# DIGITAL_OUTPUT_2CH.net
KiCad netlist of a schematic drawn in Altium Designer
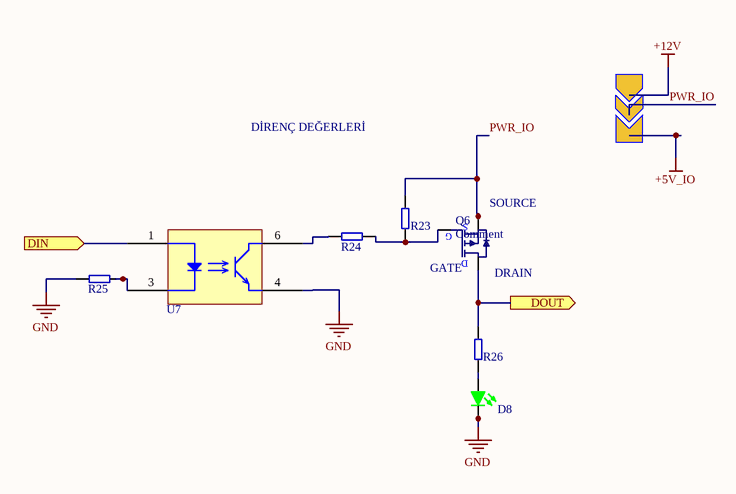
[diagram p0: DIGITAL_OUTPUT_2CH.SchDoc]

(export (version "E")
  (design (tool "Eeschema 10.0.6"))
  (components
    (comp (ref "D8")
      (value "SML-LX0603GW-TR")
      (footprint "L0603")
      (description "LED GREEN DIFFUSED SMD")
      (fields (field (name "MANUFACTURER") "Lumex Opto/Components Inc."))
      (libsource (lib "anayurt") (part "LED_GREEN"))
    )
    (comp (ref "JMP2")
      (value "Jumper")
      (footprint "SB0402_3PAD")
      (description "0402 Solder Bridge 3 PAD")
      (fields (field (name "PART NUMBER") "Solder Bridge0402_3pad"))
      (libsource (lib "anayurt") (part "3PAD_BRIDGE"))
    )
    (comp (ref "Q6")
      (value "Comment")
      (footprint "SOT-23-3")
      (description "20V 5A 28mΩ@4.5V,5A 1.3W 1.1V@250μA P Channel")
      (fields (field (name "PART NUMBER") "RU20P7C"))
      (libsource (lib "anayurt") (part "PMOS"))
    )
    (comp (ref "R23")
      (value "1K")
      (footprint "R0402")
      (description "RES SMD 1K OHM 0.1% 1/16W 0402")
      (fields (field (name "PART NUMBER") "RT0402BRE071KL") (field (name "TOLERANCE") "0.1%"))
      (libsource (lib "anayurt") (part "RES"))
    )
    (comp (ref "R24")
      (value "1K")
      (footprint "R0402")
      (description "RES SMD 1K OHM 0.1% 1/16W 0402")
      (fields (field (name "PART NUMBER") "RT0402BRE071KL") (field (name "TOLERANCE") "0.1%"))
      (libsource (lib "anayurt") (part "RES"))
    )
    (comp (ref "R25")
      (value "1K")
      (footprint "R0402")
      (description "RES SMD 1K OHM 0.1% 1/16W 0402")
      (fields (field (name "PART NUMBER") "RT0402BRE071KL") (field (name "TOLERANCE") "0.1%"))
      (libsource (lib "anayurt") (part "RES"))
    )
    (comp (ref "R26")
      (value "4.7K")
      (footprint "R0402")
      (description "RES SMD 4.7K OHM 1% 1/16W 0402")
      (fields (field (name "PART NUMBER") "CRCW04024K70FKED") (field (name "TOLERANCE") "0.1%"))
      (libsource (lib "anayurt") (part "RES"))
    )
    (comp (ref "U7")
      (value "TLP183(BLL-TPL,E")
      (footprint "TLP183(BLL-TPL,E")
      (description "OPTOISO 3.75KV TRANS 6-SO 4 LEAD")
      (fields (field (name "MANUFACTURER") "Toshiba"))
      (libsource (lib "anayurt") (part "TLP183(BLL-TPL,E"))
    )
  )
  (nets
    (net (code "1") (name "+5V_IO") (class "Default")
      (node (ref "JMP2") (pin "3") (pinfunction "3_3") (pintype "passive"))
    )
    (net (code "2") (name "+12V") (class "Default")
      (node (ref "JMP2") (pin "1") (pinfunction "1_1") (pintype "passive"))
    )
    (net (code "3") (name "/DIN") (class "Default")
      (node (ref "U7") (pin "1") (pinfunction "A_1") (pintype "passive"))
    )
    (net (code "4") (name "/DOUT") (class "Default")
      (node (ref "Q6") (pin "3") (pinfunction "D_3") (pintype "passive"))
      (node (ref "R26") (pin "2") (pinfunction "2_2") (pintype "passive"))
    )
    (net (code "5") (name "/PWR_IO") (class "Default")
      (node (ref "JMP2") (pin "2") (pinfunction "2_2") (pintype "passive"))
      (node (ref "Q6") (pin "2") (pinfunction "S_2") (pintype "passive"))
      (node (ref "R23") (pin "1") (pinfunction "1_1") (pintype "passive"))
    )
    (net (code "6") (name "GND") (class "Default")
      (node (ref "D8") (pin "C") (pinfunction "C_C") (pintype "passive"))
      (node (ref "R25") (pin "1") (pinfunction "1_1") (pintype "passive"))
      (node (ref "U7") (pin "4") (pinfunction "Emi_4") (pintype "passive"))
    )
    (net (code "7") (name "Net-(D8-PadA)") (class "Default")
      (node (ref "D8") (pin "A") (pinfunction "A_A") (pintype "passive"))
      (node (ref "R26") (pin "1") (pinfunction "1_1") (pintype "passive"))
    )
    (net (code "8") (name "Net-(Q6-G)") (class "Default")
      (node (ref "Q6") (pin "1") (pinfunction "G_1") (pintype "passive"))
      (node (ref "R23") (pin "2") (pinfunction "2_2") (pintype "passive"))
      (node (ref "R24") (pin "2") (pinfunction "2_2") (pintype "passive"))
    )
    (net (code "9") (name "Net-(U7-C)") (class "Default")
      (node (ref "R25") (pin "2") (pinfunction "2_2") (pintype "passive"))
      (node (ref "U7") (pin "3") (pinfunction "C_3") (pintype "passive"))
    )
    (net (code "10") (name "Net-(U7-Col)") (class "Default")
      (node (ref "R24") (pin "1") (pinfunction "1_1") (pintype "passive"))
      (node (ref "U7") (pin "6") (pinfunction "Col_6") (pintype "passive"))
    )
  )
)
